# Pg2_Battery_Contacts.net
KiCad netlist of a schematic drawn in Altium Designer
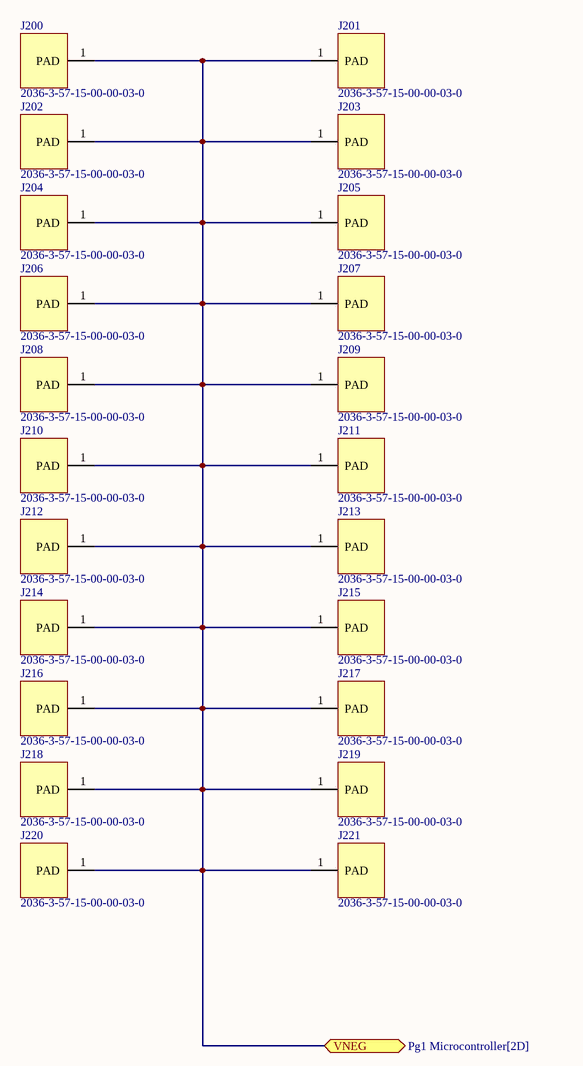
[diagram p0: Pg2 Battery Contacts.SchDoc]

(export (version "E")
  (design (tool "Eeschema 10.0.6"))
  (components
    (comp (ref "J200")
      (value "2036-3-57-15-00-00-03-0")
      (footprint "6mm Pad")
      (description "Hardware, Sprint Contact Surface")
      (libsource (lib "") (part "2036-3-57-15-00-00-03-0_1"))
    )
    (comp (ref "J201")
      (value "2036-3-57-15-00-00-03-0")
      (footprint "6mm Pad")
      (description "Hardware, Sprint Contact Surface")
      (libsource (lib "SchLib - EE391 Master") (part "2036-3-57-15-00-00-03-0"))
    )
    (comp (ref "J202")
      (value "2036-3-57-15-00-00-03-0")
      (footprint "6mm Pad")
      (description "Hardware, Sprint Contact Surface")
      (libsource (lib "") (part "2036-3-57-15-00-00-03-0_1"))
    )
    (comp (ref "J203")
      (value "2036-3-57-15-00-00-03-0")
      (footprint "6mm Pad")
      (description "Hardware, Sprint Contact Surface")
      (libsource (lib "SchLib - EE391 Master") (part "2036-3-57-15-00-00-03-0"))
    )
    (comp (ref "J204")
      (value "2036-3-57-15-00-00-03-0")
      (footprint "6mm Pad")
      (description "Hardware, Sprint Contact Surface")
      (libsource (lib "") (part "2036-3-57-15-00-00-03-0_1"))
    )
    (comp (ref "J205")
      (value "2036-3-57-15-00-00-03-0")
      (footprint "6mm Pad")
      (description "Hardware, Sprint Contact Surface")
      (libsource (lib "SchLib - EE391 Master") (part "2036-3-57-15-00-00-03-0"))
    )
    (comp (ref "J206")
      (value "2036-3-57-15-00-00-03-0")
      (footprint "6mm Pad")
      (description "Hardware, Sprint Contact Surface")
      (libsource (lib "") (part "2036-3-57-15-00-00-03-0_1"))
    )
    (comp (ref "J207")
      (value "2036-3-57-15-00-00-03-0")
      (footprint "6mm Pad")
      (description "Hardware, Sprint Contact Surface")
      (libsource (lib "SchLib - EE391 Master") (part "2036-3-57-15-00-00-03-0"))
    )
    (comp (ref "J208")
      (value "2036-3-57-15-00-00-03-0")
      (footprint "6mm Pad")
      (description "Hardware, Sprint Contact Surface")
      (libsource (lib "") (part "2036-3-57-15-00-00-03-0_1"))
    )
    (comp (ref "J209")
      (value "2036-3-57-15-00-00-03-0")
      (footprint "6mm Pad")
      (description "Hardware, Sprint Contact Surface")
      (libsource (lib "SchLib - EE391 Master") (part "2036-3-57-15-00-00-03-0"))
    )
    (comp (ref "J210")
      (value "2036-3-57-15-00-00-03-0")
      (footprint "6mm Pad")
      (description "Hardware, Sprint Contact Surface")
      (libsource (lib "") (part "2036-3-57-15-00-00-03-0_1"))
    )
    (comp (ref "J211")
      (value "2036-3-57-15-00-00-03-0")
      (footprint "6mm Pad")
      (description "Hardware, Sprint Contact Surface")
      (libsource (lib "SchLib - EE391 Master") (part "2036-3-57-15-00-00-03-0"))
    )
    (comp (ref "J212")
      (value "2036-3-57-15-00-00-03-0")
      (footprint "6mm Pad")
      (description "Hardware, Sprint Contact Surface")
      (libsource (lib "") (part "2036-3-57-15-00-00-03-0_1"))
    )
    (comp (ref "J213")
      (value "2036-3-57-15-00-00-03-0")
      (footprint "6mm Pad")
      (description "Hardware, Sprint Contact Surface")
      (libsource (lib "SchLib - EE391 Master") (part "2036-3-57-15-00-00-03-0"))
    )
    (comp (ref "J214")
      (value "2036-3-57-15-00-00-03-0")
      (footprint "6mm Pad")
      (description "Hardware, Sprint Contact Surface")
      (libsource (lib "") (part "2036-3-57-15-00-00-03-0_1"))
    )
    (comp (ref "J215")
      (value "2036-3-57-15-00-00-03-0")
      (footprint "6mm Pad")
      (description "Hardware, Sprint Contact Surface")
      (libsource (lib "SchLib - EE391 Master") (part "2036-3-57-15-00-00-03-0"))
    )
    (comp (ref "J216")
      (value "2036-3-57-15-00-00-03-0")
      (footprint "6mm Pad")
      (description "Hardware, Sprint Contact Surface")
      (libsource (lib "") (part "2036-3-57-15-00-00-03-0_1"))
    )
    (comp (ref "J217")
      (value "2036-3-57-15-00-00-03-0")
      (footprint "6mm Pad")
      (description "Hardware, Sprint Contact Surface")
      (libsource (lib "SchLib - EE391 Master") (part "2036-3-57-15-00-00-03-0"))
    )
    (comp (ref "J218")
      (value "2036-3-57-15-00-00-03-0")
      (footprint "6mm Pad")
      (description "Hardware, Sprint Contact Surface")
      (libsource (lib "") (part "2036-3-57-15-00-00-03-0_1"))
    )
    (comp (ref "J219")
      (value "2036-3-57-15-00-00-03-0")
      (footprint "6mm Pad")
      (description "Hardware, Sprint Contact Surface")
      (libsource (lib "SchLib - EE391 Master") (part "2036-3-57-15-00-00-03-0"))
    )
    (comp (ref "J220")
      (value "2036-3-57-15-00-00-03-0")
      (footprint "6mm Pad")
      (description "Hardware, Sprint Contact Surface")
      (libsource (lib "") (part "2036-3-57-15-00-00-03-0_1"))
    )
    (comp (ref "J221")
      (value "2036-3-57-15-00-00-03-0")
      (footprint "6mm Pad")
      (description "Hardware, Sprint Contact Surface")
      (libsource (lib "SchLib - EE391 Master") (part "2036-3-57-15-00-00-03-0"))
    )
  )
  (nets
    (net (code "1") (name "/VNEG") (class "Default")
      (node (ref "J200") (pin "1") (pinfunction "PAD_1") (pintype "passive"))
      (node (ref "J201") (pin "1") (pinfunction "PAD_1") (pintype "passive"))
      (node (ref "J202") (pin "1") (pinfunction "PAD_1") (pintype "passive"))
      (node (ref "J203") (pin "1") (pinfunction "PAD_1") (pintype "passive"))
      (node (ref "J204") (pin "1") (pinfunction "PAD_1") (pintype "passive"))
      (node (ref "J205") (pin "1") (pinfunction "PAD_1") (pintype "passive"))
      (node (ref "J206") (pin "1") (pinfunction "PAD_1") (pintype "passive"))
      (node (ref "J207") (pin "1") (pinfunction "PAD_1") (pintype "passive"))
      (node (ref "J208") (pin "1") (pinfunction "PAD_1") (pintype "passive"))
      (node (ref "J209") (pin "1") (pinfunction "PAD_1") (pintype "passive"))
      (node (ref "J210") (pin "1") (pinfunction "PAD_1") (pintype "passive"))
      (node (ref "J211") (pin "1") (pinfunction "PAD_1") (pintype "passive"))
      (node (ref "J212") (pin "1") (pinfunction "PAD_1") (pintype "passive"))
      (node (ref "J213") (pin "1") (pinfunction "PAD_1") (pintype "passive"))
      (node (ref "J214") (pin "1") (pinfunction "PAD_1") (pintype "passive"))
      (node (ref "J215") (pin "1") (pinfunction "PAD_1") (pintype "passive"))
      (node (ref "J216") (pin "1") (pinfunction "PAD_1") (pintype "passive"))
      (node (ref "J217") (pin "1") (pinfunction "PAD_1") (pintype "passive"))
      (node (ref "J218") (pin "1") (pinfunction "PAD_1") (pintype "passive"))
      (node (ref "J219") (pin "1") (pinfunction "PAD_1") (pintype "passive"))
      (node (ref "J220") (pin "1") (pinfunction "PAD_1") (pintype "passive"))
      (node (ref "J221") (pin "1") (pinfunction "PAD_1") (pintype "passive"))
    )
  )
)
